# main_schematic_correction.net
KiCad netlist of a schematic drawn in EAGLE
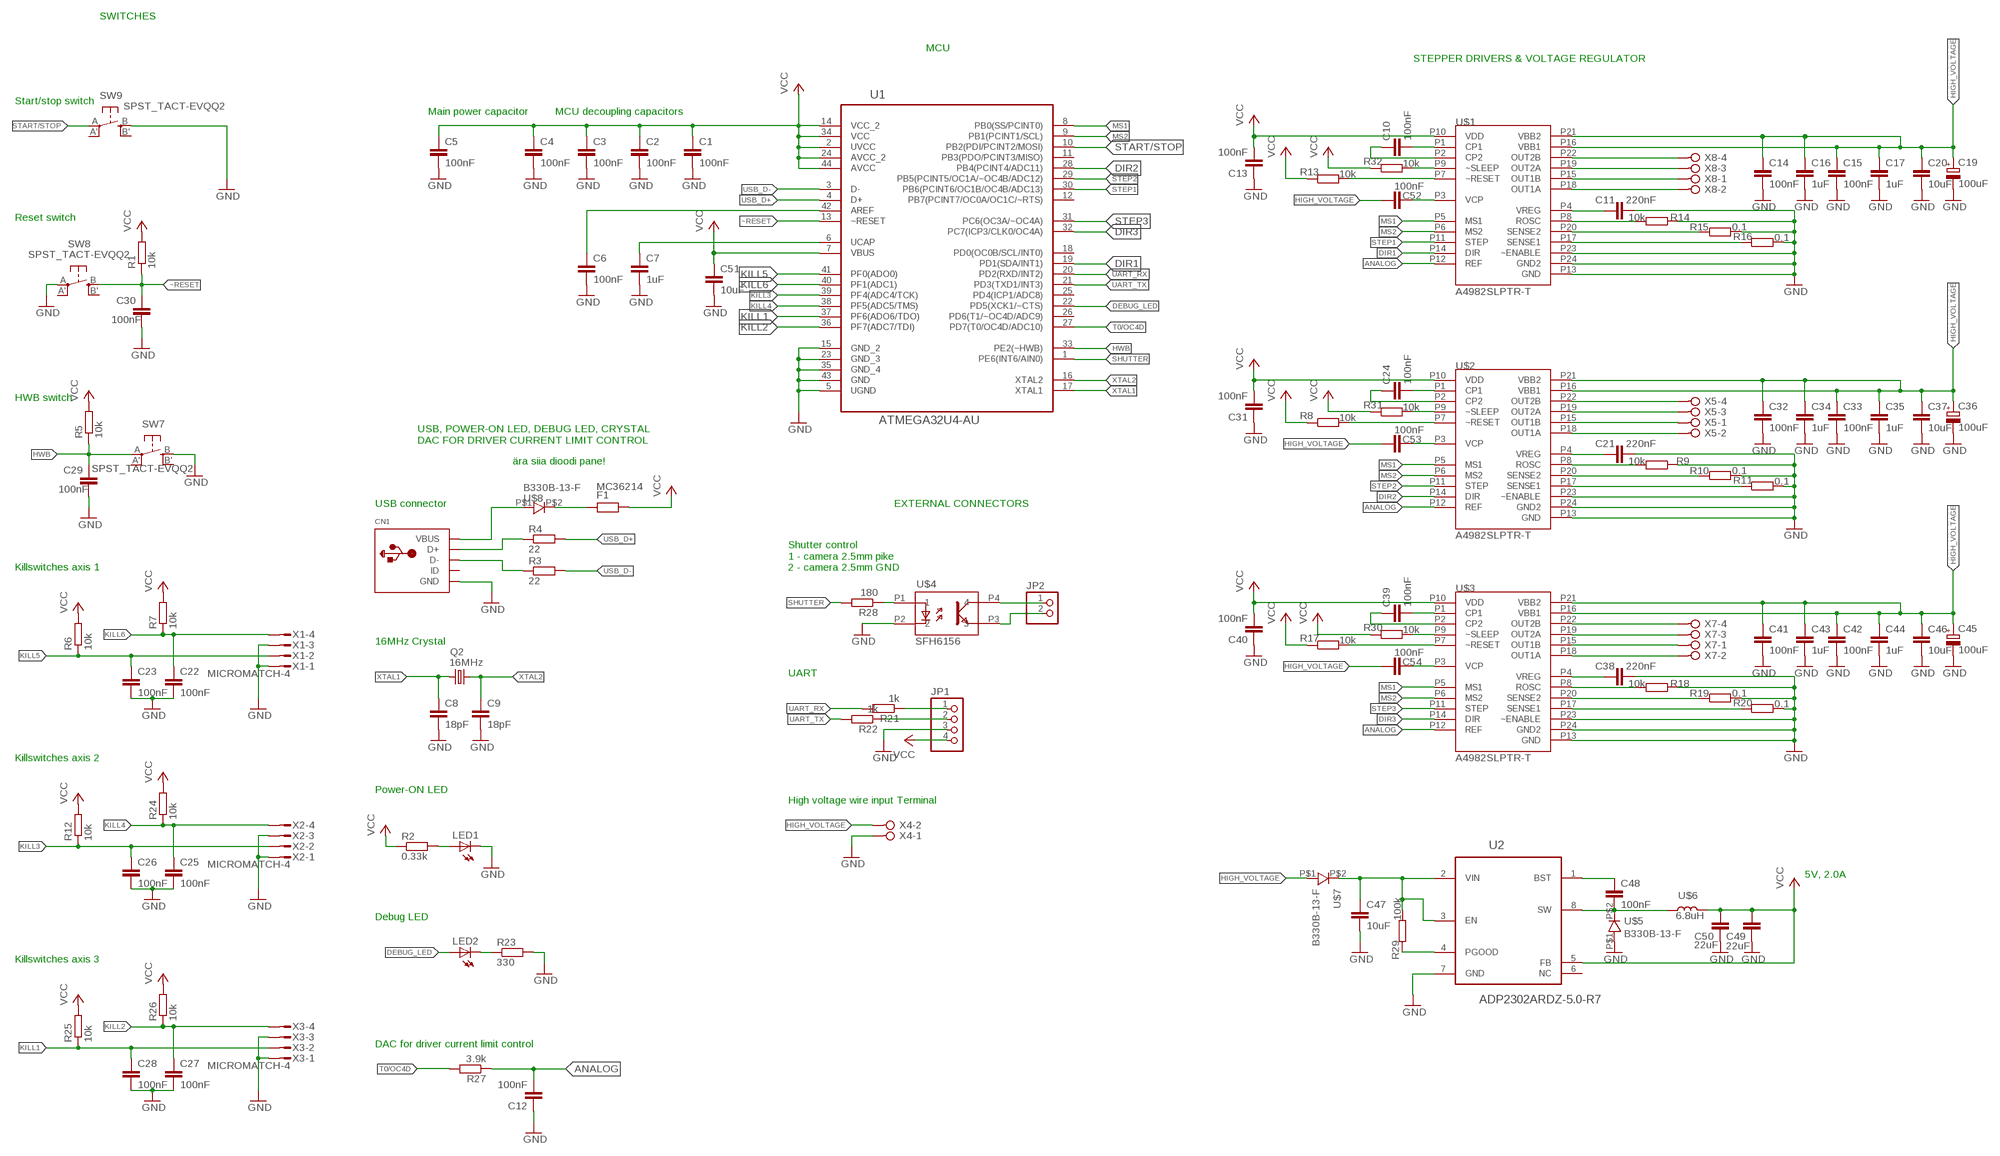
[diagram p0: schematic, sheet 1]

(export (version "E")
  (design (tool "Eeschema 10.0.6"))
  (components
    (comp (ref "C1")
      (value "100nF")
      (footprint "eagle-import:C0603K")
      (libsource (lib "eagle-import") (part "C-EUC0603K"))
    )
    (comp (ref "C2")
      (value "100nF")
      (footprint "eagle-import:C0603K")
      (libsource (lib "eagle-import") (part "C-EUC0603K"))
    )
    (comp (ref "C3")
      (value "100nF")
      (footprint "eagle-import:C0603K")
      (libsource (lib "eagle-import") (part "C-EUC0603K"))
    )
    (comp (ref "C4")
      (value "100nF")
      (footprint "eagle-import:C0603K")
      (libsource (lib "eagle-import") (part "C-EUC0603K"))
    )
    (comp (ref "C5")
      (value "100nF")
      (footprint "eagle-import:C0603K")
      (libsource (lib "eagle-import") (part "C-EUC0603K"))
    )
    (comp (ref "C6")
      (value "100nF")
      (footprint "eagle-import:C0603K")
      (libsource (lib "eagle-import") (part "C-EUC0603K"))
    )
    (comp (ref "C7")
      (value "1uF")
      (footprint "eagle-import:C0603K")
      (libsource (lib "eagle-import") (part "C-EUC0603K"))
    )
    (comp (ref "C8")
      (value "18pF")
      (footprint "eagle-import:C0603K")
      (libsource (lib "eagle-import") (part "C-EUC0603K"))
    )
    (comp (ref "C9")
      (value "18pF")
      (footprint "eagle-import:C0603K")
      (libsource (lib "eagle-import") (part "C-EUC0603K"))
    )
    (comp (ref "C10")
      (value "100nF")
      (footprint "eagle-import:C0603K")
      (libsource (lib "eagle-import") (part "C-EUC0603K"))
    )
    (comp (ref "C11")
      (value "220nF")
      (footprint "eagle-import:C0603K")
      (libsource (lib "eagle-import") (part "C-EUC0603K"))
    )
    (comp (ref "C12")
      (value "100nF")
      (footprint "eagle-import:C0603K")
      (libsource (lib "eagle-import") (part "C-EUC0603K"))
    )
    (comp (ref "C13")
      (value "100nF")
      (footprint "eagle-import:C0603K")
      (libsource (lib "eagle-import") (part "C-EUC0603K"))
    )
    (comp (ref "C14")
      (value "100nF")
      (footprint "eagle-import:C0603K")
      (libsource (lib "eagle-import") (part "C-EUC0603K"))
    )
    (comp (ref "C15")
      (value "100nF")
      (footprint "eagle-import:C0603K")
      (libsource (lib "eagle-import") (part "C-EUC0603K"))
    )
    (comp (ref "C16")
      (value "1uF")
      (footprint "eagle-import:C0603K")
      (libsource (lib "eagle-import") (part "C-EUC0603K"))
    )
    (comp (ref "C17")
      (value "1uF")
      (footprint "eagle-import:C0603K")
      (libsource (lib "eagle-import") (part "C-EUC0603K"))
    )
    (comp (ref "C19")
      (value "100uF")
      (footprint "eagle-import:E_7260-38R")
      (libsource (lib "eagle-import") (part "CPOL-EUE/7260-38R"))
    )
    (comp (ref "C20")
      (value "10uF")
      (footprint "eagle-import:C1206K")
      (libsource (lib "eagle-import") (part "C-EUC1206K"))
    )
    (comp (ref "C21")
      (value "220nF")
      (footprint "eagle-import:C0603K")
      (libsource (lib "eagle-import") (part "C-EUC0603K"))
    )
    (comp (ref "C22")
      (value "100nF")
      (footprint "eagle-import:C0603K")
      (libsource (lib "eagle-import") (part "C-EUC0603K"))
    )
    (comp (ref "C23")
      (value "100nF")
      (footprint "eagle-import:C0603K")
      (libsource (lib "eagle-import") (part "C-EUC0603K"))
    )
    (comp (ref "C24")
      (value "100nF")
      (footprint "eagle-import:C0603K")
      (libsource (lib "eagle-import") (part "C-EUC0603K"))
    )
    (comp (ref "C25")
      (value "100nF")
      (footprint "eagle-import:C0603K")
      (libsource (lib "eagle-import") (part "C-EUC0603K"))
    )
    (comp (ref "C26")
      (value "100nF")
      (footprint "eagle-import:C0603K")
      (libsource (lib "eagle-import") (part "C-EUC0603K"))
    )
    (comp (ref "C27")
      (value "100nF")
      (footprint "eagle-import:C0603K")
      (libsource (lib "eagle-import") (part "C-EUC0603K"))
    )
    (comp (ref "C28")
      (value "100nF")
      (footprint "eagle-import:C0603K")
      (libsource (lib "eagle-import") (part "C-EUC0603K"))
    )
    (comp (ref "C29")
      (value "100nF")
      (footprint "eagle-import:C0603K")
      (libsource (lib "eagle-import") (part "C-EUC0603K"))
    )
    (comp (ref "C30")
      (value "100nF")
      (footprint "eagle-import:C0603K")
      (libsource (lib "eagle-import") (part "C-EUC0603K"))
    )
    (comp (ref "C31")
      (value "100nF")
      (footprint "eagle-import:C0603K")
      (libsource (lib "eagle-import") (part "C-EUC0603K"))
    )
    (comp (ref "C32")
      (value "100nF")
      (footprint "eagle-import:C0603K")
      (libsource (lib "eagle-import") (part "C-EUC0603K"))
    )
    (comp (ref "C33")
      (value "100nF")
      (footprint "eagle-import:C0603K")
      (libsource (lib "eagle-import") (part "C-EUC0603K"))
    )
    (comp (ref "C34")
      (value "1uF")
      (footprint "eagle-import:C0603K")
      (libsource (lib "eagle-import") (part "C-EUC0603K"))
    )
    (comp (ref "C35")
      (value "1uF")
      (footprint "eagle-import:C0603K")
      (libsource (lib "eagle-import") (part "C-EUC0603K"))
    )
    (comp (ref "C36")
      (value "100uF")
      (footprint "eagle-import:E_7260-38R")
      (libsource (lib "eagle-import") (part "CPOL-EUE/7260-38R"))
    )
    (comp (ref "C37")
      (value "10uF")
      (footprint "eagle-import:C1206K")
      (libsource (lib "eagle-import") (part "C-EUC1206K"))
    )
    (comp (ref "C38")
      (value "220nF")
      (footprint "eagle-import:C0603K")
      (libsource (lib "eagle-import") (part "C-EUC0603K"))
    )
    (comp (ref "C39")
      (value "100nF")
      (footprint "eagle-import:C0603K")
      (libsource (lib "eagle-import") (part "C-EUC0603K"))
    )
    (comp (ref "C40")
      (value "100nF")
      (footprint "eagle-import:C0603K")
      (libsource (lib "eagle-import") (part "C-EUC0603K"))
    )
    (comp (ref "C41")
      (value "100nF")
      (footprint "eagle-import:C0603K")
      (libsource (lib "eagle-import") (part "C-EUC0603K"))
    )
    (comp (ref "C42")
      (value "100nF")
      (footprint "eagle-import:C0603K")
      (libsource (lib "eagle-import") (part "C-EUC0603K"))
    )
    (comp (ref "C43")
      (value "1uF")
      (footprint "eagle-import:C0603K")
      (libsource (lib "eagle-import") (part "C-EUC0603K"))
    )
    (comp (ref "C44")
      (value "1uF")
      (footprint "eagle-import:C0603K")
      (libsource (lib "eagle-import") (part "C-EUC0603K"))
    )
    (comp (ref "C45")
      (value "100uF")
      (footprint "eagle-import:E_7260-38R")
      (libsource (lib "eagle-import") (part "CPOL-EUE/7260-38R"))
    )
    (comp (ref "C46")
      (value "10uF")
      (footprint "eagle-import:C1206K")
      (libsource (lib "eagle-import") (part "C-EUC1206K"))
    )
    (comp (ref "C47")
      (value "10uF")
      (footprint "eagle-import:C1206K")
      (libsource (lib "eagle-import") (part "C-EUC1206K"))
    )
    (comp (ref "C48")
      (value "100nF")
      (footprint "eagle-import:C1206K")
      (libsource (lib "eagle-import") (part "C-EUC1206K"))
    )
    (comp (ref "C49")
      (value "22uF")
      (footprint "eagle-import:C1206K")
      (libsource (lib "eagle-import") (part "C-EUC1206K"))
    )
    (comp (ref "C50")
      (value "22uF")
      (footprint "eagle-import:C1206K")
      (libsource (lib "eagle-import") (part "C-EUC1206K"))
    )
    (comp (ref "C51")
      (value "10uF")
      (footprint "eagle-import:C0805")
      (libsource (lib "eagle-import") (part "C-EUC0805"))
    )
    (comp (ref "C52")
      (value "100nF")
      (footprint "eagle-import:C0603K")
      (libsource (lib "eagle-import") (part "C-EUC0603K"))
    )
    (comp (ref "C53")
      (value "100nF")
      (footprint "eagle-import:C0603K")
      (libsource (lib "eagle-import") (part "C-EUC0603K"))
    )
    (comp (ref "C54")
      (value "100nF")
      (footprint "eagle-import:C0603K")
      (libsource (lib "eagle-import") (part "C-EUC0603K"))
    )
    (comp (ref "CN1")
      (value "USBMINIB")
      (footprint "eagle-import:USB-MINIB")
      (libsource (lib "eagle-import") (part "USBMINIB"))
    )
    (comp (ref "F1")
      (value "MC36214")
      (footprint "eagle-import:MC36214")
      (libsource (lib "eagle-import") (part "MC36214"))
    )
    (comp (ref "JP1")
      (value "PINHD-1X4")
      (footprint "eagle-import:1X04")
      (libsource (lib "eagle-import") (part "PINHD-1X4"))
    )
    (comp (ref "JP2")
      (value "PINHD-1X2")
      (footprint "eagle-import:1X02")
      (libsource (lib "eagle-import") (part "PINHD-1X2"))
    )
    (comp (ref "LED1")
      (value "LEDCHIP-LED0603")
      (footprint "eagle-import:CHIP-LED0603")
      (libsource (lib "eagle-import") (part "LEDCHIP-LED0603"))
    )
    (comp (ref "LED2")
      (value "LEDCHIP-LED0603")
      (footprint "eagle-import:CHIP-LED0603")
      (libsource (lib "eagle-import") (part "LEDCHIP-LED0603"))
    )
    (comp (ref "Q2")
      (value "16MHz")
      (footprint "eagle-import:SM49")
      (libsource (lib "eagle-import") (part "CRYSTALSM49"))
    )
    (comp (ref "R1")
      (value "10k")
      (footprint "eagle-import:R0603")
      (libsource (lib "eagle-import") (part "R-EU_R0603"))
    )
    (comp (ref "R2")
      (value "0.33k")
      (footprint "eagle-import:R0603")
      (libsource (lib "eagle-import") (part "R-EU_R0603"))
    )
    (comp (ref "R3")
      (value "22")
      (footprint "eagle-import:R0603")
      (libsource (lib "eagle-import") (part "R-EU_R0603"))
    )
    (comp (ref "R4")
      (value "22")
      (footprint "eagle-import:R0603")
      (libsource (lib "eagle-import") (part "R-EU_R0603"))
    )
    (comp (ref "R5")
      (value "10k")
      (footprint "eagle-import:R0603")
      (libsource (lib "eagle-import") (part "R-EU_R0603"))
    )
    (comp (ref "R6")
      (value "10k")
      (footprint "eagle-import:R0603")
      (libsource (lib "eagle-import") (part "R-EU_R0603"))
    )
    (comp (ref "R7")
      (value "10k")
      (footprint "eagle-import:R0603")
      (libsource (lib "eagle-import") (part "R-EU_R0603"))
    )
    (comp (ref "R8")
      (value "10k")
      (footprint "eagle-import:R0603")
      (libsource (lib "eagle-import") (part "R-EU_R0603"))
    )
    (comp (ref "R9")
      (value "10k")
      (footprint "eagle-import:R0603")
      (libsource (lib "eagle-import") (part "R-EU_R0603"))
    )
    (comp (ref "R10")
      (value "0.1")
      (footprint "eagle-import:R0805")
      (libsource (lib "eagle-import") (part "R-EU_R0805"))
    )
    (comp (ref "R11")
      (value "0.1")
      (footprint "eagle-import:R0805")
      (libsource (lib "eagle-import") (part "R-EU_R0805"))
    )
    (comp (ref "R12")
      (value "10k")
      (footprint "eagle-import:R0603")
      (libsource (lib "eagle-import") (part "R-EU_R0603"))
    )
    (comp (ref "R13")
      (value "10k")
      (footprint "eagle-import:R0603")
      (libsource (lib "eagle-import") (part "R-EU_R0603"))
    )
    (comp (ref "R14")
      (value "10k")
      (footprint "eagle-import:R0603")
      (libsource (lib "eagle-import") (part "R-EU_R0603"))
    )
    (comp (ref "R15")
      (value "0.1")
      (footprint "eagle-import:R0805")
      (libsource (lib "eagle-import") (part "R-EU_R0805"))
    )
    (comp (ref "R16")
      (value "0.1")
      (footprint "eagle-import:R0805")
      (libsource (lib "eagle-import") (part "R-EU_R0805"))
    )
    (comp (ref "R17")
      (value "10k")
      (footprint "eagle-import:R0603")
      (libsource (lib "eagle-import") (part "R-EU_R0603"))
    )
    (comp (ref "R18")
      (value "10k")
      (footprint "eagle-import:R0603")
      (libsource (lib "eagle-import") (part "R-EU_R0603"))
    )
    (comp (ref "R19")
      (value "0.1")
      (footprint "eagle-import:R0805")
      (libsource (lib "eagle-import") (part "R-EU_R0805"))
    )
    (comp (ref "R20")
      (value "0.1")
      (footprint "eagle-import:R0805")
      (libsource (lib "eagle-import") (part "R-EU_R0805"))
    )
    (comp (ref "R21")
      (value "1k")
      (footprint "eagle-import:R0603")
      (libsource (lib "eagle-import") (part "R-EU_R0603"))
    )
    (comp (ref "R22")
      (value "1k")
      (footprint "eagle-import:R0603")
      (libsource (lib "eagle-import") (part "R-EU_R0603"))
    )
    (comp (ref "R23")
      (value "330")
      (footprint "eagle-import:R0603")
      (libsource (lib "eagle-import") (part "R-EU_R0603"))
    )
    (comp (ref "R24")
      (value "10k")
      (footprint "eagle-import:R0603")
      (libsource (lib "eagle-import") (part "R-EU_R0603"))
    )
    (comp (ref "R25")
      (value "10k")
      (footprint "eagle-import:R0603")
      (libsource (lib "eagle-import") (part "R-EU_R0603"))
    )
    (comp (ref "R26")
      (value "10k")
      (footprint "eagle-import:R0603")
      (libsource (lib "eagle-import") (part "R-EU_R0603"))
    )
    (comp (ref "R27")
      (value "3.9k")
      (footprint "eagle-import:R0603")
      (libsource (lib "eagle-import") (part "R-EU_R0603"))
    )
    (comp (ref "R28")
      (value "180")
      (footprint "eagle-import:R0603")
      (libsource (lib "eagle-import") (part "R-EU_R0603"))
    )
    (comp (ref "R29")
      (value "100k")
      (footprint "eagle-import:R0603")
      (libsource (lib "eagle-import") (part "R-EU_R0603"))
    )
    (comp (ref "R30")
      (value "10k")
      (footprint "eagle-import:R0603")
      (libsource (lib "eagle-import") (part "R-EU_R0603"))
    )
    (comp (ref "R31")
      (value "10k")
      (footprint "eagle-import:R0603")
      (libsource (lib "eagle-import") (part "R-EU_R0603"))
    )
    (comp (ref "R32")
      (value "10k")
      (footprint "eagle-import:R0603")
      (libsource (lib "eagle-import") (part "R-EU_R0603"))
    )
    (comp (ref "SW7")
      (value "SPST_TACT-EVQQ2")
      (footprint "eagle-import:EVQ-Q2")
      (libsource (lib "eagle-import") (part "SPST_TACT-EVQQ2"))
    )
    (comp (ref "SW8")
      (value "SPST_TACT-EVQQ2")
      (footprint "eagle-import:EVQ-Q2")
      (libsource (lib "eagle-import") (part "SPST_TACT-EVQQ2"))
    )
    (comp (ref "SW9")
      (value "SPST_TACT-EVQQ2")
      (footprint "eagle-import:EVQ-Q2")
      (libsource (lib "eagle-import") (part "SPST_TACT-EVQQ2"))
    )
    (comp (ref "U$1")
      (value "A4982SLPTR-T")
      (footprint "eagle-import:TSSOP_24")
      (libsource (lib "eagle-import") (part "A4982SLPTR-T"))
    )
    (comp (ref "U$2")
      (value "A4982SLPTR-T")
      (footprint "eagle-import:TSSOP_24")
      (libsource (lib "eagle-import") (part "A4982SLPTR-T"))
    )
    (comp (ref "U$3")
      (value "A4982SLPTR-T")
      (footprint "eagle-import:TSSOP_24")
      (libsource (lib "eagle-import") (part "A4982SLPTR-T"))
    )
    (comp (ref "U$4")
      (value "SFH6156")
      (footprint "eagle-import:SFH6165")
      (libsource (lib "eagle-import") (part "SFH6156"))
    )
    (comp (ref "U$5")
      (value "B330B-13-F")
      (footprint "eagle-import:B330B-13-F")
      (libsource (lib "eagle-import") (part "SCHOTTK_YB330B-13-F"))
    )
    (comp (ref "U$6")
      (value "6.8uH")
      (footprint "eagle-import:VLF10040")
      (libsource (lib "eagle-import") (part "VLF10040"))
    )
    (comp (ref "U$7")
      (value "B330B-13-F")
      (footprint "eagle-import:B330B-13-F")
      (libsource (lib "eagle-import") (part "SCHOTTK_YB330B-13-F"))
    )
    (comp (ref "U$8")
      (value "B330B-13-F")
      (footprint "eagle-import:B330B-13-F")
      (libsource (lib "eagle-import") (part "SCHOTTK_YB330B-13-F"))
    )
    (comp (ref "U1")
      (value "ATMEGA32U4-AU")
      (footprint "eagle-import:QFP80P1200X1200X120-44N")
      (libsource (lib "eagle-import") (part "ATMEGA32U4-AU"))
    )
    (comp (ref "U2")
      (value "ADP2302ARDZ-5.0-R7")
      (footprint "eagle-import:SOIC127P600X175-9N")
      (libsource (lib "eagle-import") (part "ADP2302ARDZ-5.0-R7"))
    )
    (comp (ref "X1")
      (value "MICROMATCH-4")
      (footprint "eagle-import:MICROMATCH-4")
      (fields (field (name "MPN") "7-215464-4"))
      (libsource (lib "eagle-import") (part "MICROMATCH-4"))
    )
    (comp (ref "X2")
      (value "MICROMATCH-4")
      (footprint "eagle-import:MICROMATCH-4")
      (fields (field (name "MPN") "7-215464-4"))
      (libsource (lib "eagle-import") (part "MICROMATCH-4"))
    )
    (comp (ref "X3")
      (value "MICROMATCH-4")
      (footprint "eagle-import:MICROMATCH-4")
      (fields (field (name "MPN") "7-215464-4"))
      (libsource (lib "eagle-import") (part "MICROMATCH-4"))
    )
    (comp (ref "X4")
      (value "W237-02P")
      (footprint "eagle-import:W237-132")
      (libsource (lib "eagle-import") (part "W237-02P"))
    )
    (comp (ref "X5")
      (value "W237-04P")
      (footprint "eagle-import:W237-4P")
      (libsource (lib "eagle-import") (part "W237-04P"))
    )
    (comp (ref "X7")
      (value "W237-04P")
      (footprint "eagle-import:W237-4P")
      (libsource (lib "eagle-import") (part "W237-04P"))
    )
    (comp (ref "X8")
      (value "W237-04P")
      (footprint "eagle-import:W237-4P")
      (libsource (lib "eagle-import") (part "W237-04P"))
    )
  )
  (nets
    (net (code "1") (name "/~{RESET}") (class "Default")
      (node (ref "C30") (pin "1") (pinfunction "1_1") (pintype "passive"))
      (node (ref "R1") (pin "1") (pinfunction "1_1") (pintype "passive"))
      (node (ref "SW8") (pin "B") (pinfunction "S_B") (pintype "passive"))
      (node (ref "U1") (pin "13") (pinfunction "~{RESET}_13") (pintype "input"))
    )
    (net (code "2") (name "ANALOG") (class "Default")
      (node (ref "C12") (pin "2") (pinfunction "2_2") (pintype "passive"))
      (node (ref "R27") (pin "1") (pinfunction "1_1") (pintype "passive"))
      (node (ref "U$1") (pin "P12") (pinfunction "REF_P12") (pintype "bidirectional"))
      (node (ref "U$2") (pin "P12") (pinfunction "REF_P12") (pintype "bidirectional"))
      (node (ref "U$3") (pin "P12") (pinfunction "REF_P12") (pintype "bidirectional"))
    )
    (net (code "3") (name "DEBUG_LED") (class "Default")
      (node (ref "LED2") (pin "A") (pinfunction "A_A") (pintype "passive"))
      (node (ref "U1") (pin "22") (pinfunction "PD5(XCK1/~{CTS})_22") (pintype "bidirectional"))
    )
    (net (code "4") (name "DIR1") (class "Default")
      (node (ref "U$1") (pin "P14") (pinfunction "DIR_P14") (pintype "bidirectional"))
      (node (ref "U1") (pin "19") (pinfunction "PD1(SDA/INT1)_19") (pintype "bidirectional"))
    )
    (net (code "5") (name "DIR2") (class "Default")
      (node (ref "U$2") (pin "P14") (pinfunction "DIR_P14") (pintype "bidirectional"))
      (node (ref "U1") (pin "28") (pinfunction "PB4(PCINT4/ADC11)_28") (pintype "bidirectional"))
    )
    (net (code "6") (name "DIR3") (class "Default")
      (node (ref "U$3") (pin "P14") (pinfunction "DIR_P14") (pintype "bidirectional"))
      (node (ref "U1") (pin "32") (pinfunction "PC7(ICP3/CLK0/OC4A)_32") (pintype "bidirectional"))
    )
    (net (code "7") (name "GND") (class "Default")
      (node (ref "C1") (pin "2") (pinfunction "2_2") (pintype "passive"))
      (node (ref "C11") (pin "1") (pinfunction "1_1") (pintype "passive"))
      (node (ref "C12") (pin "1") (pinfunction "1_1") (pintype "passive"))
      (node (ref "C13") (pin "1") (pinfunction "1_1") (pintype "passive"))
      (node (ref "C14") (pin "2") (pinfunction "2_2") (pintype "passive"))
      (node (ref "C15") (pin "2") (pinfunction "2_2") (pintype "passive"))
      (node (ref "C16") (pin "2") (pinfunction "2_2") (pintype "passive"))
      (node (ref "C17") (pin "2") (pinfunction "2_2") (pintype "passive"))
      (node (ref "C19") (pin "-") (pinfunction "-_-") (pintype "passive"))
      (node (ref "C2") (pin "2") (pinfunction "2_2") (pintype "passive"))
      (node (ref "C20") (pin "2") (pinfunction "2_2") (pintype "passive"))
      (node (ref "C21") (pin "1") (pinfunction "1_1") (pintype "passive"))
      (node (ref "C22") (pin "2") (pinfunction "2_2") (pintype "passive"))
      (node (ref "C23") (pin "2") (pinfunction "2_2") (pintype "passive"))
      (node (ref "C25") (pin "2") (pinfunction "2_2") (pintype "passive"))
      (node (ref "C26") (pin "2") (pinfunction "2_2") (pintype "passive"))
      (node (ref "C27") (pin "2") (pinfunction "2_2") (pintype "passive"))
      (node (ref "C28") (pin "2") (pinfunction "2_2") (pintype "passive"))
      (node (ref "C29") (pin "2") (pinfunction "2_2") (pintype "passive"))
      (node (ref "C3") (pin "2") (pinfunction "2_2") (pintype "passive"))
      (node (ref "C30") (pin "2") (pinfunction "2_2") (pintype "passive"))
      (node (ref "C31") (pin "1") (pinfunction "1_1") (pintype "passive"))
      (node (ref "C32") (pin "2") (pinfunction "2_2") (pintype "passive"))
      (node (ref "C33") (pin "2") (pinfunction "2_2") (pintype "passive"))
      (node (ref "C34") (pin "2") (pinfunction "2_2") (pintype "passive"))
      (node (ref "C35") (pin "2") (pinfunction "2_2") (pintype "passive"))
      (node (ref "C36") (pin "-") (pinfunction "-_-") (pintype "passive"))
      (node (ref "C37") (pin "2") (pinfunction "2_2") (pintype "passive"))
      (node (ref "C38") (pin "1") (pinfunction "1_1") (pintype "passive"))
      (node (ref "C4") (pin "2") (pinfunction "2_2") (pintype "passive"))
      (node (ref "C40") (pin "1") (pinfunction "1_1") (pintype "passive"))
      (node (ref "C41") (pin "2") (pinfunction "2_2") (pintype "passive"))
      (node (ref "C42") (pin "2") (pinfunction "2_2") (pintype "passive"))
      (node (ref "C43") (pin "2") (pinfunction "2_2") (pintype "passive"))
      (node (ref "C44") (pin "2") (pinfunction "2_2") (pintype "passive"))
      (node (ref "C45") (pin "-") (pinfunction "-_-") (pintype "passive"))
      (node (ref "C46") (pin "2") (pinfunction "2_2") (pintype "passive"))
      (node (ref "C47") (pin "2") (pinfunction "2_2") (pintype "passive"))
      (node (ref "C49") (pin "1") (pinfunction "1_1") (pintype "passive"))
      (node (ref "C5") (pin "2") (pinfunction "2_2") (pintype "passive"))
      (node (ref "C50") (pin "1") (pinfunction "1_1") (pintype "passive"))
      (node (ref "C51") (pin "2") (pinfunction "2_2") (pintype "passive"))
      (node (ref "C6") (pin "2") (pinfunction "2_2") (pintype "passive"))
      (node (ref "C7") (pin "2") (pinfunction "2_2") (pintype "passive"))
      (node (ref "C8") (pin "2") (pinfunction "2_2") (pintype "passive"))
      (node (ref "C9") (pin "2") (pinfunction "2_2") (pintype "passive"))
      (node (ref "CN1") (pin "GND") (pinfunction "GND_GND") (pintype "power_in"))
      (node (ref "JP1") (pin "3") (pinfunction "3_3") (pintype "passive"))
      (node (ref "LED1") (pin "C") (pinfunction "C_C") (pintype "passive"))
      (node (ref "R10") (pin "2") (pinfunction "2_2") (pintype "passive"))
      (node (ref "R11") (pin "2") (pinfunction "2_2") (pintype "passive"))
      (node (ref "R14") (pin "1") (pinfunction "1_1") (pintype "passive"))
      (node (ref "R15") (pin "2") (pinfunction "2_2") (pintype "passive"))
      (node (ref "R16") (pin "2") (pinfunction "2_2") (pintype "passive"))
      (node (ref "R18") (pin "1") (pinfunction "1_1") (pintype "passive"))
      (node (ref "R19") (pin "2") (pinfunction "2_2") (pintype "passive"))
      (node (ref "R20") (pin "2") (pinfunction "2_2") (pintype "passive"))
      (node (ref "R23") (pin "2") (pinfunction "2_2") (pintype "passive"))
      (node (ref "R9") (pin "1") (pinfunction "1_1") (pintype "passive"))
      (node (ref "SW7") (pin "B") (pinfunction "S_B") (pintype "passive"))
      (node (ref "SW8") (pin "A") (pinfunction "P_A") (pintype "passive"))
      (node (ref "SW9") (pin "B") (pinfunction "S_B") (pintype "passive"))
      (node (ref "U$1") (pin "P13") (pinfunction "GND_P13") (pintype "bidirectional"))
      (node (ref "U$1") (pin "P23") (pinfunction "~{ENABLE}_P23") (pintype "bidirectional"))
      (node (ref "U$1") (pin "P24") (pinfunction "GND2_P24") (pintype "bidirectional"))
      (node (ref "U$2") (pin "P13") (pinfunction "GND_P13") (pintype "bidirectional"))
      (node (ref "U$2") (pin "P23") (pinfunction "~{ENABLE}_P23") (pintype "bidirectional"))
      (node (ref "U$2") (pin "P24") (pinfunction "GND2_P24") (pintype "bidirectional"))
      (node (ref "U$3") (pin "P13") (pinfunction "GND_P13") (pintype "bidirectional"))
      (node (ref "U$3") (pin "P23") (pinfunction "~{ENABLE}_P23") (pintype "bidirectional"))
      (node (ref "U$3") (pin "P24") (pinfunction "GND2_P24") (pintype "bidirectional"))
      (node (ref "U$4") (pin "P2") (pinfunction "2_P2") (pintype "bidirectional"))
      (node (ref "U$5") (pin "P$1") (pinfunction "P$1_P$1") (pintype "bidirectional"))
      (node (ref "U1") (pin "15") (pinfunction "GND_2_15") (pintype "passive"))
      (node (ref "U1") (pin "23") (pinfunction "GND_3_23") (pintype "passive"))
      (node (ref "U1") (pin "35") (pinfunction "GND_4_35") (pintype "passive"))
      (node (ref "U1") (pin "43") (pinfunction "GND_43") (pintype "passive"))
      (node (ref "U1") (pin "5") (pinfunction "UGND_5") (pintype "passive"))
      (node (ref "U2") (pin "7") (pinfunction "GND_7") (pintype "passive"))
      (node (ref "X1") (pin "1") (pinfunction "S_1") (pintype "passive"))
      (node (ref "X1") (pin "3") (pinfunction "S_3") (pintype "passive"))
      (node (ref "X2") (pin "1") (pinfunction "S_1") (pintype "passive"))
      (node (ref "X2") (pin "3") (pinfunction "S_3") (pintype "passive"))
      (node (ref "X3") (pin "1") (pinfunction "S_1") (pintype "passive"))
      (node (ref "X3") (pin "3") (pinfunction "S_3") (pintype "passive"))
      (node (ref "X4") (pin "1") (pinfunction "KL_1") (pintype "passive"))
    )
    (net (code "8") (name "HIGH_VOLTAGE") (class "Default")
      (node (ref "C14") (pin "1") (pinfunction "1_1") (pintype "passive"))
      (node (ref "C15") (pin "1") (pinfunction "1_1") (pintype "passive"))
      (node (ref "C16") (pin "1") (pinfunction "1_1") (pintype "passive"))
      (node (ref "C17") (pin "1") (pinfunction "1_1") (pintype "passive"))
      (node (ref "C19") (pin "+") (pinfunction "+_+") (pintype "passive"))
      (node (ref "C20") (pin "1") (pinfunction "1_1") (pintype "passive"))
      (node (ref "C32") (pin "1") (pinfunction "1_1") (pintype "passive"))
      (node (ref "C33") (pin "1") (pinfunction "1_1") (pintype "passive"))
      (node (ref "C34") (pin "1") (pinfunction "1_1") (pintype "passive"))
      (node (ref "C35") (pin "1") (pinfunction "1_1") (pintype "passive"))
      (node (ref "C36") (pin "+") (pinfunction "+_+") (pintype "passive"))
      (node (ref "C37") (pin "1") (pinfunction "1_1") (pintype "passive"))
      (node (ref "C41") (pin "1") (pinfunction "1_1") (pintype "passive"))
      (node (ref "C42") (pin "1") (pinfunction "1_1") (pintype "passive"))
      (node (ref "C43") (pin "1") (pinfunction "1_1") (pintype "passive"))
      (node (ref "C44") (pin "1") (pinfunction "1_1") (pintype "passive"))
      (node (ref "C45") (pin "+") (pinfunction "+_+") (pintype "passive"))
      (node (ref "C46") (pin "1") (pinfunction "1_1") (pintype "passive"))
      (node (ref "U$1") (pin "P16") (pinfunction "VBB1_P16") (pintype "bidirectional"))
      (node (ref "U$1") (pin "P21") (pinfunction "VBB2_P21") (pintype "bidirectional"))
      (node (ref "U$2") (pin "P16") (pinfunction "VBB1_P16") (pintype "bidirectional"))
      (node (ref "U$2") (pin "P21") (pinfunction "VBB2_P21") (pintype "bidirectional"))
      (node (ref "U$3") (pin "P16") (pinfunction "VBB1_P16") (pintype "bidirectional"))
      (node (ref "U$3") (pin "P21") (pinfunction "VBB2_P21") (pintype "bidirectional"))
      (node (ref "U$7") (pin "P$1") (pinfunction "P$1_P$1") (pintype "bidirectional"))
      (node (ref "X4") (pin "2") (pinfunction "KL_2") (pintype "passive"))
    )
    (net (code "9") (name "HWB") (class "Default")
      (node (ref "C29") (pin "1") (pinfunction "1_1") (pintype "passive"))
      (node (ref "R5") (pin "1") (pinfunction "1_1") (pintype "passive"))
      (node (ref "SW7") (pin "A") (pinfunction "P_A") (pintype "passive"))
      (node (ref "U1") (pin "33") (pinfunction "PE2(~{HWB})_33") (pintype "bidirectional"))
    )
    (net (code "10") (name "KILL1") (class "Default")
      (node (ref "C28") (pin "1") (pinfunction "1_1") (pintype "passive"))
      (node (ref "R25") (pin "1") (pinfunction "1_1") (pintype "passive"))
      (node (ref "U1") (pin "37") (pinfunction "PF6(ADO6/TDO)_37") (pintype "bidirectional"))
      (node (ref "X3") (pin "2") (pinfunction "S_2") (pintype "passive"))
    )
    (net (code "11") (name "KILL2") (class "Default")
      (node (ref "C27") (pin "1") (pinfunction "1_1") (pintype "passive"))
      (node (ref "R26") (pin "1") (pinfunction "1_1") (pintype "passive"))
      (node (ref "U1") (pin "36") (pinfunction "PF7(ADC7/TDI)_36") (pintype "bidirectional"))
      (node (ref "X3") (pin "4") (pinfunction "S_4") (pintype "passive"))
    )
    (net (code "12") (name "KILL3") (class "Default")
      (node (ref "C26") (pin "1") (pinfunction "1_1") (pintype "passive"))
      (node (ref "R12") (pin "1") (pinfunction "1_1") (pintype "passive"))
      (node (ref "U1") (pin "39") (pinfunction "PF4(ADC4/TCK)_39") (pintype "bidirectional"))
      (node (ref "X2") (pin "2") (pinfunction "S_2") (pintype "passive"))
    )
    (net (code "13") (name "KILL4") (class "Default")
      (node (ref "C25") (pin "1") (pinfunction "1_1") (pintype "passive"))
      (node (ref "R24") (pin "1") (pinfunction "1_1") (pintype "passive"))
      (node (ref "U1") (pin "38") (pinfunction "PF5(ADC5/TMS)_38") (pintype "bidirectional"))
      (node (ref "X2") (pin "4") (pinfunction "S_4") (pintype "passive"))
    )
    (net (code "14") (name "KILL5") (class "Default")
      (node (ref "C23") (pin "1") (pinfunction "1_1") (pintype "passive"))
      (node (ref "R6") (pin "1") (pinfunction "1_1") (pintype "passive"))
      (node (ref "U1") (pin "41") (pinfunction "PF0(ADO0)_41") (pintype "bidirectional"))
      (node (ref "X1") (pin "2") (pinfunction "S_2") (pintype "passive"))
    )
    (net (code "15") (name "KILL6") (class "Default")
      (node (ref "C22") (pin "1") (pinfunction "1_1") (pintype "passive"))
      (node (ref "R7") (pin "1") (pinfunction "1_1") (pintype "passive"))
      (node (ref "U1") (pin "40") (pinfunction "PF1(ADC1)_40") (pintype "bidirectional"))
      (node (ref "X1") (pin "4") (pinfunction "S_4") (pintype "passive"))
    )
    (net (code "16") (name "MS1") (class "Default")
      (node (ref "U$1") (pin "P5") (pinfunction "MS1_P5") (pintype "bidirectional"))
      (node (ref "U$2") (pin "P5") (pinfunction "MS1_P5") (pintype "bidirectional"))
      (node (ref "U$3") (pin "P5") (pinfunction "MS1_P5") (pintype "bidirectional"))
      (node (ref "U1") (pin "8") (pinfunction "PB0(SS/PCINT0)_8") (pintype "bidirectional"))
    )
    (net (code "17") (name "MS2") (class "Default")
      (node (ref "U$1") (pin "P6") (pinfunction "MS2_P6") (pintype "bidirectional"))
      (node (ref "U$2") (pin "P6") (pinfunction "MS2_P6") (pintype "bidirectional"))
      (node (ref "U$3") (pin "P6") (pinfunction "MS2_P6") (pintype "bidirectional"))
      (node (ref "U1") (pin "9") (pinfunction "PB1(PCINT1/SCL)_9") (pintype "bidirectional"))
    )
    (net (code "18") (name "Net-(CN1-PadD+)") (class "Default")
      (node (ref "CN1") (pin "D+") (pinfunction "D+_D+") (pintype "bidirectional"))
      (node (ref "R4") (pin "1") (pinfunction "1_1") (pintype "passive"))
    )
    (net (code "19") (name "Net-(CN1-PadD-)") (class "Default")
      (node (ref "CN1") (pin "D-") (pinfunction "D-_D-") (pintype "bidirectional"))
      (node (ref "R3") (pin "1") (pinfunction "1_1") (pintype "passive"))
    )
    (net (code "20") (name "Net-(CN1-PadVBUS)") (class "Default")
      (node (ref "CN1") (pin "VBUS") (pinfunction "VBUS_VBUS") (pintype "power_in"))
      (node (ref "U$8") (pin "P$1") (pinfunction "P$1_P$1") (pintype "bidirectional"))
    )
    (net (code "21") (name "Net-(F1-PadP$1)") (class "Default")
      (node (ref "F1") (pin "P$1") (pinfunction "P$1_P$1") (pintype "bidirectional"))
      (node (ref "U$8") (pin "P$2") (pinfunction "P$2_P$2") (pintype "bidirectional"))
    )
    (net (code "22") (name "Net-(JP1-Pad1)") (class "Default")
      (node (ref "JP1") (pin "1") (pinfunction "1_1") (pintype "passive"))
      (node (ref "R21") (pin "1") (pinfunction "1_1") (pintype "passive"))
    )
    (net (code "23") (name "Net-(JP1-Pad2)") (class "Default")
      (node (ref "JP1") (pin "2") (pinfunction "2_2") (pintype "passive"))
      (node (ref "R22") (pin "1") (pinfunction "1_1") (pintype "passive"))
    )
    (net (code "24") (name "Net-(LED1-PadA)") (class "Default")
      (node (ref "LED1") (pin "A") (pinfunction "A_A") (pintype "passive"))
      (node (ref "R2") (pin "2") (pinfunction "2_2") (pintype "passive"))
    )
    (net (code "25") (name "Net-(LED2-PadC)") (class "Default")
      (node (ref "LED2") (pin "C") (pinfunction "C_C") (pintype "passive"))
      (node (ref "R23") (pin "1") (pinfunction "1_1") (pintype "passive"))
    )
    (net (code "26") (name "Net-(U$1-CP1)") (class "Default")
      (node (ref "C10") (pin "2") (pinfunction "2_2") (pintype "passive"))
      (node (ref "U$1") (pin "P1") (pinfunction "CP1_P1") (pintype "bidirectional"))
    )
    (net (code "27") (name "Net-(U$1-CP2)") (class "Default")
      (node (ref "C10") (pin "1") (pinfunction "1_1") (pintype "passive"))
      (node (ref "U$1") (pin "P2") (pinfunction "CP2_P2") (pintype "bidirectional"))
    )
    (net (code "28") (name "Net-(U$1-OUT1A)") (class "Default")
      (node (ref "U$1") (pin "P18") (pinfunction "OUT1A_P18") (pintype "bidirectional"))
      (node (ref "X8") (pin "2") (pinfunction "KL_2") (pintype "passive"))
    )
    (net (code "29") (name "Net-(U$1-OUT1B)") (class "Default")
      (node (ref "U$1") (pin "P15") (pinfunction "OUT1B_P15") (pintype "bidirectional"))
      (node (ref "X8") (pin "1") (pinfunction "KL_1") (pintype "passive"))
    )
    (net (code "30") (name "Net-(U$1-OUT2A)") (class "Default")
      (node (ref "U$1") (pin "P19") (pinfunction "OUT2A_P19") (pintype "bidirectional"))
      (node (ref "X8") (pin "3") (pinfunction "KL_3") (pintype "passive"))
    )
    (net (code "31") (name "Net-(U$1-OUT2B)") (class "Default")
      (node (ref "U$1") (pin "P22") (pinfunction "OUT2B_P22") (pintype "bidirectional"))
      (node (ref "X8") (pin "4") (pinfunction "KL_4") (pintype "passive"))
    )
    (net (code "32") (name "Net-(U$1-ROSC)") (class "Default")
      (node (ref "R14") (pin "2") (pinfunction "2_2") (pintype "passive"))
      (node (ref "U$1") (pin "P8") (pinfunction "ROSC_P8") (pintype "bidirectional"))
    )
    (net (code "33") (name "Net-(U$1-SENSE1)") (class "Default")
      (node (ref "R16") (pin "1") (pinfunction "1_1") (pintype "passive"))
      (node (ref "U$1") (pin "P17") (pinfunction "SENSE1_P17") (pintype "bidirectional"))
    )
    (net (code "34") (name "Net-(U$1-SENSE2)") (class "Default")
      (node (ref "R15") (pin "1") (pinfunction "1_1") (pintype "passive"))
      (node (ref "U$1") (pin "P20") (pinfunction "SENSE2_P20") (pintype "bidirectional"))
    )
    (net (code "35") (name "Net-(U$1-VCP)") (class "Default")
      (node (ref "C52") (pin "1") (pinfunction "1_1") (pintype "passive"))
      (node (ref "U$1") (pin "P3") (pinfunction "VCP_P3") (pintype "bidirectional"))
    )
    (net (code "36") (name "Net-(U$1-VREG)") (class "Default")
      (node (ref "C11") (pin "2") (pinfunction "2_2") (pintype "passive"))
      (node (ref "U$1") (pin "P4") (pinfunction "VREG_P4") (pintype "bidirectional"))
    )
    (net (code "37") (name "Net-(U$1-~{RESET})") (class "Default")
      (node (ref "R13") (pin "2") (pinfunction "2_2") (pintype "passive"))
      (node (ref "U$1") (pin "P7") (pinfunction "~{RESET}_P7") (pintype "bidirectional"))
    )
    (net (code "38") (name "Net-(U$1-~{SLEEP})") (class "Default")
      (node (ref "R32") (pin "2") (pinfunction "2_2") (pintype "passive"))
      (node (ref "U$1") (pin "P9") (pinfunction "~{SLEEP}_P9") (pintype "bidirectional"))
    )
    (net (code "39") (name "Net-(U$2-CP1)") (class "Default")
      (node (ref "C24") (pin "2") (pinfunction "2_2") (pintype "passive"))
      (node (ref "U$2") (pin "P1") (pinfunction "CP1_P1") (pintype "bidirectional"))
    )
    (net (code "40") (name "Net-(U$2-CP2)") (class "Default")
      (node (ref "C24") (pin "1") (pinfunction "1_1") (pintype "passive"))
      (node (ref "U$2") (pin "P2") (pinfunction "CP2_P2") (pintype "bidirectional"))
    )
    (net (code "41") (name "Net-(U$2-OUT1A)") (class "Default")
      (node (ref "U$2") (pin "P18") (pinfunction "OUT1A_P18") (pintype "bidirectional"))
      (node (ref "X5") (pin "2") (pinfunction "KL_2") (pintype "passive"))
    )
    (net (code "42") (name "Net-(U$2-OUT1B)") (class "Default")
      (node (ref "U$2") (pin "P15") (pinfunction "OUT1B_P15") (pintype "bidirectional"))
      (node (ref "X5") (pin "1") (pinfunction "KL_1") (pintype "passive"))
    )
    (net (code "43") (name "Net-(U$2-OUT2A)") (class "Default")
      (node (ref "U$2") (pin "P19") (pinfunction "OUT2A_P19") (pintype "bidirectional"))
      (node (ref "X5") (pin "3") (pinfunction "KL_3") (pintype "passive"))
    )
    (net (code "44") (name "Net-(U$2-OUT2B)") (class "Default")
      (node (ref "U$2") (pin "P22") (pinfunction "OUT2B_P22") (pintype "bidirectional"))
      (node (ref "X5") (pin "4") (pinfunction "KL_4") (pintype "passive"))
    )
    (net (code "45") (name "Net-(U$2-ROSC)") (class "Default")
      (node (ref "R9") (pin "2") (pinfunction "2_2") (pintype "passive"))
      (node (ref "U$2") (pin "P8") (pinfunction "ROSC_P8") (pintype "bidirectional"))
    )
    (net (code "46") (name "Net-(U$2-SENSE1)") (class "Default")
      (node (ref "R11") (pin "1") (pinfunction "1_1") (pintype "passive"))
      (node (ref "U$2") (pin "P17") (pinfunction "SENSE1_P17") (pintype "bidirectional"))
    )
    (net (code "47") (name "Net-(U$2-SENSE2)") (class "Default")
      (node (ref "R10") (pin "1") (pinfunction "1_1") (pintype "passive"))
      (node (ref "U$2") (pin "P20") (pinfunction "SENSE2_P20") (pintype "bidirectional"))
    )
    (net (code "48") (name "Net-(U$2-VCP)") (class "Default")
      (node (ref "C53") (pin "1") (pinfunction "1_1") (pintype "passive"))
      (node (ref "U$2") (pin "P3") (pinfunction "VCP_P3") (pintype "bidirectional"))
    )
    (net (code "49") (name "Net-(U$2-VREG)") (class "Default")
      (node (ref "C21") (pin "2") (pinfunction "2_2") (pintype "passive"))
      (node (ref "U$2") (pin "P4") (pinfunction "VREG_P4") (pintype "bidirectional"))
    )
    (net (code "50") (name "Net-(U$2-~{RESET})") (class "Default")
      (node (ref "R8") (pin "2") (pinfunction "2_2") (pintype "passive"))
      (node (ref "U$2") (pin "P7") (pinfunction "~{RESET}_P7") (pintype "bidirectional"))
    )
    (net (code "51") (name "Net-(U$2-~{SLEEP})") (class "Default")
      (node (ref "R31") (pin "2") (pinfunction "2_2") (pintype "passive"))
      (node (ref "U$2") (pin "P9") (pinfunction "~{SLEEP}_P9") (pintype "bidirectional"))
    )
    (net (code "52") (name "Net-(U$3-CP1)") (class "Default")
      (node (ref "C39") (pin "2") (pinfunction "2_2") (pintype "passive"))
      (node (ref "U$3") (pin "P1") (pinfunction "CP1_P1") (pintype "bidirectional"))
    )
    (net (code "53") (name "Net-(U$3-CP2)") (class "Default")
      (node (ref "C39") (pin "1") (pinfunction "1_1") (pintype "passive"))
      (node (ref "U$3") (pin "P2") (pinfunction "CP2_P2") (pintype "bidirectional"))
    )
    (net (code "54") (name "Net-(U$3-OUT1A)") (class "Default")
      (node (ref "U$3") (pin "P18") (pinfunction "OUT1A_P18") (pintype "bidirectional"))
      (node (ref "X7") (pin "2") (pinfunction "KL_2") (pintype "passive"))
    )
    (net (code "55") (name "Net-(U$3-OUT1B)") (class "Default")
      (node (ref "U$3") (pin "P15") (pinfunction "OUT1B_P15") (pintype "bidirectional"))
      (node (ref "X7") (pin "1") (pinfunction "KL_1") (pintype "passive"))
    )
    (net (code "56") (name "Net-(U$3-OUT2A)") (class "Default")
      (node (ref "U$3") (pin "P19") (pinfunction "OUT2A_P19") (pintype "bidirectional"))
      (node (ref "X7") (pin "3") (pinfunction "KL_3") (pintype "passive"))
    )
    (net (code "57") (name "Net-(U$3-OUT2B)") (class "Default")
      (node (ref "U$3") (pin "P22") (pinfunction "OUT2B_P22") (pintype "bidirectional"))
      (node (ref "X7") (pin "4") (pinfunction "KL_4") (pintype "passive"))
    )
    (net (code "58") (name "Net-(U$3-ROSC)") (class "Default")
      (node (ref "R18") (pin "2") (pinfunction "2_2") (pintype "passive"))
      (node (ref "U$3") (pin "P8") (pinfunction "ROSC_P8") (pintype "bidirectional"))
    )
    (net (code "59") (name "Net-(U$3-SENSE1)") (class "Default")
      (node (ref "R20") (pin "1") (pinfunction "1_1") (pintype "passive"))
      (node (ref "U$3") (pin "P17") (pinfunction "SENSE1_P17") (pintype "bidirectional"))
    )
    (net (code "60") (name "Net-(U$3-SENSE2)") (class "Default")
      (node (ref "R19") (pin "1") (pinfunction "1_1") (pintype "passive"))
      (node (ref "U$3") (pin "P20") (pinfunction "SENSE2_P20") (pintype "bidirectional"))
    )
    (net (code "61") (name "Net-(U$3-VCP)") (class "Default")
      (node (ref "C54") (pin "1") (pinfunction "1_1") (pintype "passive"))
      (node (ref "U$3") (pin "P3") (pinfunction "VCP_P3") (pintype "bidirectional"))
    )
    (net (code "62") (name "Net-(U$3-VREG)") (class "Default")
      (node (ref "C38") (pin "2") (pinfunction "2_2") (pintype "passive"))
      (node (ref "U$3") (pin "P4") (pinfunction "VREG_P4") (pintype "bidirectional"))
    )
    (net (code "63") (name "Net-(U$3-~{RESET})") (class "Default")
      (node (ref "R17") (pin "2") (pinfunction "2_2") (pintype "passive"))
      (node (ref "U$3") (pin "P7") (pinfunction "~{RESET}_P7") (pintype "bidirectional"))
    )
    (net (code "64") (name "Net-(U$3-~{SLEEP})") (class "Default")
      (node (ref "R30") (pin "2") (pinfunction "2_2") (pintype "passive"))
      (node (ref "U$3") (pin "P9") (pinfunction "~{SLEEP}_P9") (pintype "bidirectional"))
    )
    (net (code "65") (name "Net-(U$4-1)") (class "Default")
      (node (ref "R28") (pin "1") (pinfunction "1_1") (pintype "passive"))
      (node (ref "U$4") (pin "P1") (pinfunction "1_P1") (pintype "bidirectional"))
    )
    (net (code "66") (name "Net-(U$4-3)") (class "Default")
      (node (ref "JP2") (pin "2") (pinfunction "2_2") (pintype "passive"))
      (node (ref "U$4") (pin "P3") (pinfunction "3_P3") (pintype "bidirectional"))
    )
    (net (code "67") (name "Net-(U$4-4)") (class "Default")
      (node (ref "JP2") (pin "1") (pinfunction "1_1") (pintype "passive"))
      (node (ref "U$4") (pin "P4") (pinfunction "4_P4") (pintype "bidirectional"))
    )
    (net (code "68") (name "Net-(U1-AREF)") (class "Default")
      (node (ref "C6") (pin "1") (pinfunction "1_1") (pintype "passive"))
      (node (ref "U1") (pin "42") (pinfunction "AREF_42") (pintype "input"))
    )
    (net (code "69") (name "Net-(U1-UCAP)") (class "Default")
      (node (ref "C7") (pin "1") (pinfunction "1_1") (pintype "passive"))
      (node (ref "U1") (pin "6") (pinfunction "UCAP_6") (pintype "power_in"))
    )
    (net (code "70") (name "Net-(U2-BST)") (class "Default")
      (node (ref "C48") (pin "1") (pinfunction "1_1") (pintype "passive"))
      (node (ref "U2") (pin "1") (pinfunction "BST_1") (pintype "power_in"))
    )
    (net (code "71") (name "Net-(U2-EN)") (class "Default")
      (node (ref "C47") (pin "1") (pinfunction "1_1") (pintype "passive"))
      (node (ref "R29") (pin "2") (pinfunction "2_2") (pintype "passive"))
      (node (ref "U$7") (pin "P$2") (pinfunction "P$2_P$2") (pintype "bidirectional"))
      (node (ref "U2") (pin "2") (pinfunction "VIN_2") (pintype "power_in"))
      (node (ref "U2") (pin "3") (pinfunction "EN_3") (pintype "input"))
    )
    (net (code "72") (name "Net-(U2-PGOOD)") (class "Default")
      (node (ref "R29") (pin "1") (pinfunction "1_1") (pintype "passive"))
      (node (ref "U2") (pin "4") (pinfunction "PGOOD_4") (pintype "output"))
    )
    (net (code "73") (name "Net-(U2-SW)") (class "Default")
      (node (ref "C48") (pin "2") (pinfunction "2_2") (pintype "passive"))
      (node (ref "U$5") (pin "P$2") (pinfunction "P$2_P$2") (pintype "bidirectional"))
      (node (ref "U$6") (pin "P$2") (pinfunction "P$2_P$2") (pintype "bidirectional"))
      (node (ref "U2") (pin "8") (pinfunction "SW_8") (pintype "output"))
    )
    (net (code "74") (name "SHUTTER") (class "Default")
      (node (ref "R28") (pin "2") (pinfunction "2_2") (pintype "passive"))
      (node (ref "U1") (pin "1") (pinfunction "PE6(INT6/AIN0)_1") (pintype "bidirectional"))
    )
    (net (code "75") (name "START{slash}STOP") (class "Default")
      (node (ref "SW9") (pin "A") (pinfunction "P_A") (pintype "passive"))
      (node (ref "U1") (pin "10") (pinfunction "PB2(PDI/PCINT2/MOSI)_10") (pintype "bidirectional"))
    )
    (net (code "76") (name "STEP1") (class "Default")
      (node (ref "U$1") (pin "P11") (pinfunction "STEP_P11") (pintype "bidirectional"))
      (node (ref "U1") (pin "30") (pinfunction "PB6(PCINT6/OC1B/OC4B/ADC13)_30") (pintype "bidirectional"))
    )
    (net (code "77") (name "STEP2") (class "Default")
      (node (ref "U$2") (pin "P11") (pinfunction "STEP_P11") (pintype "bidirectional"))
      (node (ref "U1") (pin "29") (pinfunction "PB5(PCINT5/OC1A/~{OC4B/ADC12})_29") (pintype "bidirectional"))
    )
    (net (code "78") (name "STEP3") (class "Default")
      (node (ref "U$3") (pin "P11") (pinfunction "STEP_P11") (pintype "bidirectional"))
      (node (ref "U1") (pin "31") (pinfunction "PC6(OC3A/~{OC4A})_31") (pintype "bidirectional"))
    )
    (net (code "79") (name "T0{slash}OC4D") (class "Default")
      (node (ref "R27") (pin "2") (pinfunction "2_2") (pintype "passive"))
      (node (ref "U1") (pin "27") (pinfunction "PD7(T0/OC4D/ADC10)_27") (pintype "bidirectional"))
    )
    (net (code "80") (name "UART_RX") (class "Default")
      (node (ref "R21") (pin "2") (pinfunction "2_2") (pintype "passive"))
      (node (ref "U1") (pin "20") (pinfunction "PD2(RXD/INT2)_20") (pintype "bidirectional"))
    )
    (net (code "81") (name "UART_TX") (class "Default")
      (node (ref "R22") (pin "2") (pinfunction "2_2") (pintype "passive"))
      (node (ref "U1") (pin "21") (pinfunction "PD3(TXD1/INT3)_21") (pintype "bidirectional"))
    )
    (net (code "82") (name "USB_D+") (class "Default")
      (node (ref "R4") (pin "2") (pinfunction "2_2") (pintype "passive"))
      (node (ref "U1") (pin "4") (pinfunction "D+_4") (pintype "passive"))
    )
    (net (code "83") (name "USB_D-") (class "Default")
      (node (ref "R3") (pin "2") (pinfunction "2_2") (pintype "passive"))
      (node (ref "U1") (pin "3") (pinfunction "D-_3") (pintype "passive"))
    )
    (net (code "84") (name "VCC") (class "Default")
      (node (ref "C1") (pin "1") (pinfunction "1_1") (pintype "passive"))
      (node (ref "C13") (pin "2") (pinfunction "2_2") (pintype "passive"))
      (node (ref "C2") (pin "1") (pinfunction "1_1") (pintype "passive"))
      (node (ref "C3") (pin "1") (pinfunction "1_1") (pintype "passive"))
      (node (ref "C31") (pin "2") (pinfunction "2_2") (pintype "passive"))
      (node (ref "C4") (pin "1") (pinfunction "1_1") (pintype "passive"))
      (node (ref "C40") (pin "2") (pinfunction "2_2") (pintype "passive"))
      (node (ref "C49") (pin "2") (pinfunction "2_2") (pintype "passive"))
      (node (ref "C5") (pin "1") (pinfunction "1_1") (pintype "passive"))
      (node (ref "C50") (pin "2") (pinfunction "2_2") (pintype "passive"))
      (node (ref "C51") (pin "1") (pinfunction "1_1") (pintype "passive"))
      (node (ref "F1") (pin "P$2") (pinfunction "P$2_P$2") (pintype "bidirectional"))
      (node (ref "JP1") (pin "4") (pinfunction "4_4") (pintype "passive"))
      (node (ref "R1") (pin "2") (pinfunction "2_2") (pintype "passive"))
      (node (ref "R12") (pin "2") (pinfunction "2_2") (pintype "passive"))
      (node (ref "R13") (pin "1") (pinfunction "1_1") (pintype "passive"))
      (node (ref "R17") (pin "1") (pinfunction "1_1") (pintype "passive"))
      (node (ref "R2") (pin "1") (pinfunction "1_1") (pintype "passive"))
      (node (ref "R24") (pin "2") (pinfunction "2_2") (pintype "passive"))
      (node (ref "R25") (pin "2") (pinfunction "2_2") (pintype "passive"))
      (node (ref "R26") (pin "2") (pinfunction "2_2") (pintype "passive"))
      (node (ref "R30") (pin "1") (pinfunction "1_1") (pintype "passive"))
      (node (ref "R31") (pin "1") (pinfunction "1_1") (pintype "passive"))
      (node (ref "R32") (pin "1") (pinfunction "1_1") (pintype "passive"))
      (node (ref "R5") (pin "2") (pinfunction "2_2") (pintype "passive"))
      (node (ref "R6") (pin "2") (pinfunction "2_2") (pintype "passive"))
      (node (ref "R7") (pin "2") (pinfunction "2_2") (pintype "passive"))
      (node (ref "R8") (pin "1") (pinfunction "1_1") (pintype "passive"))
      (node (ref "U$1") (pin "P10") (pinfunction "VDD_P10") (pintype "bidirectional"))
      (node (ref "U$2") (pin "P10") (pinfunction "VDD_P10") (pintype "bidirectional"))
      (node (ref "U$3") (pin "P10") (pinfunction "VDD_P10") (pintype "bidirectional"))
      (node (ref "U$6") (pin "P$1") (pinfunction "P$1_P$1") (pintype "bidirectional"))
      (node (ref "U1") (pin "14") (pinfunction "VCC_2_14") (pintype "power_in"))
      (node (ref "U1") (pin "2") (pinfunction "UVCC_2") (pintype "power_in"))
      (node (ref "U1") (pin "24") (pinfunction "AVCC_2_24") (pintype "power_in"))
      (node (ref "U1") (pin "34") (pinfunction "VCC_34") (pintype "power_in"))
      (node (ref "U1") (pin "44") (pinfunction "AVCC_44") (pintype "power_in"))
      (node (ref "U1") (pin "7") (pinfunction "VBUS_7") (pintype "input"))
      (node (ref "U2") (pin "5") (pinfunction "FB_5") (pintype "input"))
    )
    (net (code "85") (name "XTAL1") (class "Default")
      (node (ref "C8") (pin "1") (pinfunction "1_1") (pintype "passive"))
      (node (ref "Q2") (pin "1") (pinfunction "1_1") (pintype "passive"))
      (node (ref "U1") (pin "17") (pinfunction "XTAL1_17") (pintype "input"))
    )
    (net (code "86") (name "XTAL2") (class "Default")
      (node (ref "C9") (pin "1") (pinfunction "1_1") (pintype "passive"))
      (node (ref "Q2") (pin "2") (pinfunction "2_2") (pintype "passive"))
      (node (ref "U1") (pin "16") (pinfunction "XTAL2_16") (pintype "output"))
    )
    (net (code "87") (name "unconnected-(C52-Pad2)") (class "Default")
      (node (ref "C52") (pin "2") (pinfunction "2_2") (pintype "passive"))
    )
    (net (code "88") (name "unconnected-(C53-Pad2)") (class "Default")
      (node (ref "C53") (pin "2") (pinfunction "2_2") (pintype "passive"))
    )
    (net (code "89") (name "unconnected-(C54-Pad2)") (class "Default")
      (node (ref "C54") (pin "2") (pinfunction "2_2") (pintype "passive"))
    )
    (net (code "90") (name "unconnected-(CN1-PadID)") (class "Default")
      (node (ref "CN1") (pin "ID") (pinfunction "ID_ID") (pintype "bidirectional"))
    )
    (net (code "91") (name "unconnected-(SW7-P1-PadA')") (class "Default")
      (node (ref "SW7") (pin "A'") (pinfunction "P1_A'") (pintype "passive"))
    )
    (net (code "92") (name "unconnected-(SW7-S1-PadB')") (class "Default")
      (node (ref "SW7") (pin "B'") (pinfunction "S1_B'") (pintype "passive"))
    )
    (net (code "93") (name "unconnected-(SW8-P1-PadA')") (class "Default")
      (node (ref "SW8") (pin "A'") (pinfunction "P1_A'") (pintype "passive"))
    )
    (net (code "94") (name "unconnected-(SW8-S1-PadB')") (class "Default")
      (node (ref "SW8") (pin "B'") (pinfunction "S1_B'") (pintype "passive"))
    )
    (net (code "95") (name "unconnected-(SW9-P1-PadA')") (class "Default")
      (node (ref "SW9") (pin "A'") (pinfunction "P1_A'") (pintype "passive"))
    )
    (net (code "96") (name "unconnected-(SW9-S1-PadB')") (class "Default")
      (node (ref "SW9") (pin "B'") (pinfunction "S1_B'") (pintype "passive"))
    )
    (net (code "97") (name "unconnected-(U1-PB3(PDO{slash}PCINT3{slash}MISO)-Pad11)") (class "Default")
      (node (ref "U1") (pin "11") (pinfunction "PB3(PDO/PCINT3/MISO)_11") (pintype "bidirectional"))
    )
    (net (code "98") (name "unconnected-(U1-PB7(PCINT7{slash}OC0A{slash}OC1C{slash}~{RTS})-Pad12)") (class "Default")
      (node (ref "U1") (pin "12") (pinfunction "PB7(PCINT7/OC0A/OC1C/~{RTS})_12") (pintype "bidirectional"))
    )
    (net (code "99") (name "unconnected-(U1-PD0(OC0B{slash}SCL{slash}INT0)-Pad18)") (class "Default")
      (node (ref "U1") (pin "18") (pinfunction "PD0(OC0B/SCL/INT0)_18") (pintype "bidirectional"))
    )
    (net (code "100") (name "unconnected-(U1-PD4(ICP1{slash}ADC8)-Pad25)") (class "Default")
      (node (ref "U1") (pin "25") (pinfunction "PD4(ICP1/ADC8)_25") (pintype "bidirectional"))
    )
    (net (code "101") (name "unconnected-(U1-PD6(T1{slash}~{OC4D{slash}ADC9})-Pad26)") (class "Default")
      (node (ref "U1") (pin "26") (pinfunction "PD6(T1/~{OC4D/ADC9})_26") (pintype "bidirectional"))
    )
    (net (code "102") (name "unconnected-(U2-NC-Pad6)") (class "Default")
      (node (ref "U2") (pin "6") (pinfunction "NC_6") (pintype "no_connect"))
    )
  )
)
